# DC-DC_5V0_To_3V3.net
KiCad netlist of a schematic drawn in Altium Designer
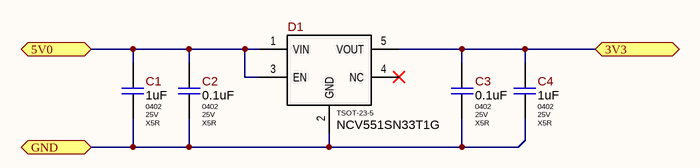
[diagram p0: DC-DC_5V0_To_3V3.SchDoc]

(export (version "E")
  (design (tool "Eeschema 10.0.6"))
  (components
    (comp (ref "C1")
      (value "1uF")
      (footprint "C_CERAMIC_0402_MED")
      (description "1uF 25V Х5R ±10% 0402 Ceramic Capacitor RoHS")
      (fields
        (field (name "PACKAGE") "0402")
        (field (name "VOLTAGE") "25V")
        (field (name "DIELECTRIC TYPE") "X5R")
        (field (name "PART NUMBER") "GRM155R61E105KA12D")
        (field (name "MANUFACTURER") "Murata Electronics")
      )
      (libsource (lib "EL.XXX.T01") (part "Capacitor-NonPolar"))
    )
    (comp (ref "C2")
      (value "0.1uF")
      (footprint "C_CERAMIC_0402_MED")
      (description "100nF 25V X5R ±10% 0402 Ceramic Capacitor RoHS")
      (fields
        (field (name "PACKAGE") "0402")
        (field (name "VOLTAGE") "25V")
        (field (name "DIELECTRIC TYPE") "X5R")
        (field (name "PART NUMBER") "CL05A104KA5NNNC")
        (field (name "MANUFACTURER") "Samsung Electro-Mechanics")
      )
      (libsource (lib "EL.XXX.T01") (part "Capacitor-NonPolar"))
    )
    (comp (ref "C3")
      (value "0.1uF")
      (footprint "C_CERAMIC_0402_MED")
      (description "100nF 25V X5R ±10% 0402 Ceramic Capacitor RoHS")
      (fields
        (field (name "PACKAGE") "0402")
        (field (name "VOLTAGE") "25V")
        (field (name "DIELECTRIC TYPE") "X5R")
        (field (name "PART NUMBER") "CL05A104KA5NNNC")
        (field (name "MANUFACTURER") "Samsung Electro-Mechanics")
      )
      (libsource (lib "EL.XXX.T01") (part "Capacitor-NonPolar"))
    )
    (comp (ref "C4")
      (value "1uF")
      (footprint "C_CERAMIC_0402_MED")
      (description "1uF 25V Х5R ±10% 0402 Ceramic Capacitor RoHS")
      (fields
        (field (name "PACKAGE") "0402")
        (field (name "VOLTAGE") "25V")
        (field (name "DIELECTRIC TYPE") "X5R")
        (field (name "PART NUMBER") "GRM155R61E105KA12D")
        (field (name "MANUFACTURER") "Murata Electronics")
      )
      (libsource (lib "EL.XXX.T01") (part "Capacitor-NonPolar"))
    )
    (comp (ref "D1")
      (value "NCV551SN33T1G")
      (footprint "TSOT-23-5")
      (description "Fixed 3.3V, 150mA Output, 12V max Input, 4uA Iq, LDO, TSOT-23-5")
      (fields
        (field (name "PACKAGE") "TSOT-23-5")
        (field (name "PART NUMBER") "NCV551SN33T1G")
        (field (name "MANUFACTURER") "Onsemi")
      )
      (libsource (lib "EL.XXX.T01") (part "NCV551SNxxT1G"))
    )
  )
  (nets
    (net (code "1") (name "/3V3") (class "Default")
      (node (ref "C3") (pin "1") (pinfunction "1_1") (pintype "passive"))
      (node (ref "C4") (pin "1") (pinfunction "1_1") (pintype "passive"))
      (node (ref "D1") (pin "5") (pinfunction "VOUT_5") (pintype "passive"))
    )
    (net (code "2") (name "/5V0") (class "Default")
      (node (ref "C1") (pin "1") (pinfunction "1_1") (pintype "passive"))
      (node (ref "C2") (pin "1") (pinfunction "1_1") (pintype "passive"))
      (node (ref "D1") (pin "1") (pinfunction "VIN_1") (pintype "passive"))
      (node (ref "D1") (pin "3") (pinfunction "EN_3") (pintype "passive"))
    )
    (net (code "3") (name "/GND") (class "Default")
      (node (ref "C1") (pin "2") (pinfunction "2_2") (pintype "passive"))
      (node (ref "C2") (pin "2") (pinfunction "2_2") (pintype "passive"))
      (node (ref "C3") (pin "2") (pinfunction "2_2") (pintype "passive"))
      (node (ref "C4") (pin "2") (pinfunction "2_2") (pintype "passive"))
      (node (ref "D1") (pin "2") (pinfunction "GND_2") (pintype "passive"))
    )
    (net (code "4") (name "unconnected-(D1-NC-Pad4)") (class "Default")
      (node (ref "D1") (pin "4") (pinfunction "NC_4") (pintype "passive+no_connect"))
    )
  )
)
